# lab3_schematic.net
KiCad netlist of a schematic drawn in Altium Designer
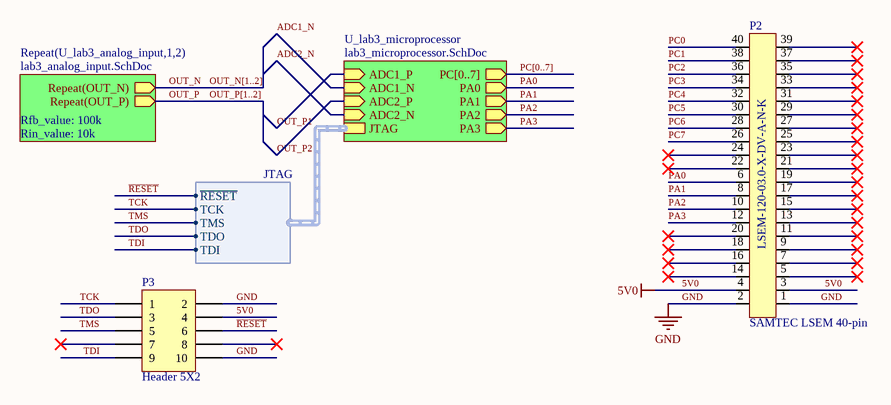
[diagram p0: lab3_schematic.SchDoc]

(export (version "E")
  (design (tool "Eeschema 10.0.6"))
  (components
    (comp (ref "P2")
      (value "SAMTEC LSEM 40-pin")
      (footprint "PcbLib_MW:LSEM-120-03.0-L-DV-A-N-K-TR")
      (fields (field (name "MANUFACTURER") "SAMTEC") (field (name "PART NUMBER") "LSEM-120-03.0-X-DV-A-N-K"))
      (libsource (lib "Schlib_MW") (part "LSEM-120-03.0-X-DV-A-N-K"))
    )
    (comp (ref "P3")
      (value "Header 5X2")
      (footprint "HDR2X5")
      (description "Header, 5-Pin, Dual row")
      (fields (field (name "PUBLISHER") "Altium Limited"))
      (libsource (lib "Miscellaneous Connectors") (part "Header 5X2"))
    )
  )
  (nets
    (net (code "12") (name "/PA0") (class "Default")
      (node (ref "P2") (pin "6") (pinfunction "4_6") (pintype "passive"))
    )
    (net (code "13") (name "/PA1") (class "Default")
      (node (ref "P2") (pin "8") (pinfunction "5_8") (pintype "passive"))
    )
    (net (code "14") (name "/PA2") (class "Default")
      (node (ref "P2") (pin "10") (pinfunction "6_10") (pintype "passive"))
    )
    (net (code "15") (name "/PA3") (class "Default")
      (node (ref "P2") (pin "12") (pinfunction "7_12") (pintype "passive"))
    )
    (net (code "16") (name "/PC0") (class "Default")
      (node (ref "P2") (pin "40") (pinfunction "21_40") (pintype "passive"))
    )
    (net (code "17") (name "/PC1") (class "Default")
      (node (ref "P2") (pin "38") (pinfunction "20_38") (pintype "passive"))
    )
    (net (code "18") (name "/PC2") (class "Default")
      (node (ref "P2") (pin "36") (pinfunction "19_36") (pintype "passive"))
    )
    (net (code "19") (name "/PC3") (class "Default")
      (node (ref "P2") (pin "34") (pinfunction "18_34") (pintype "passive"))
    )
    (net (code "20") (name "/PC4") (class "Default")
      (node (ref "P2") (pin "32") (pinfunction "17_32") (pintype "passive"))
    )
    (net (code "21") (name "/PC5") (class "Default")
      (node (ref "P2") (pin "30") (pinfunction "16_30") (pintype "passive"))
    )
    (net (code "22") (name "/PC6") (class "Default")
      (node (ref "P2") (pin "28") (pinfunction "15_28") (pintype "passive"))
    )
    (net (code "23") (name "/PC7") (class "Default")
      (node (ref "P2") (pin "26") (pinfunction "14_26") (pintype "passive"))
    )
    (net (code "25") (name "/TCK") (class "Default")
      (node (ref "P3") (pin "1") (pinfunction "1_1") (pintype "passive"))
    )
    (net (code "26") (name "/TDI") (class "Default")
      (node (ref "P3") (pin "9") (pinfunction "9_9") (pintype "passive"))
    )
    (net (code "27") (name "/TDO") (class "Default")
      (node (ref "P3") (pin "3") (pinfunction "3_3") (pintype "passive"))
    )
    (net (code "28") (name "/TMS") (class "Default")
      (node (ref "P3") (pin "5") (pinfunction "5_5") (pintype "passive"))
    )
    (net (code "30") (name "/~{RESET}") (class "Default")
      (node (ref "P3") (pin "6") (pinfunction "6_6") (pintype "passive"))
    )
    (net (code "31") (name "5V0") (class "Default")
      (node (ref "P2") (pin "3") (pinfunction "2_3") (pintype "passive"))
      (node (ref "P2") (pin "4") (pinfunction "3_4") (pintype "passive"))
      (node (ref "P3") (pin "4") (pinfunction "4_4") (pintype "passive"))
    )
    (net (code "32") (name "GND") (class "Default")
      (node (ref "P2") (pin "1") (pinfunction "1_1") (pintype "passive"))
      (node (ref "P2") (pin "2") (pinfunction "2_2") (pintype "passive"))
      (node (ref "P3") (pin "10") (pinfunction "10_10") (pintype "passive"))
      (node (ref "P3") (pin "2") (pinfunction "2_2") (pintype "passive"))
    )
    (net (code "33") (name "unconnected-(P2-3-Pad5)") (class "Default")
      (node (ref "P2") (pin "5") (pinfunction "3_5") (pintype "passive+no_connect"))
    )
    (net (code "34") (name "unconnected-(P2-4-Pad7)") (class "Default")
      (node (ref "P2") (pin "7") (pinfunction "4_7") (pintype "passive+no_connect"))
    )
    (net (code "35") (name "unconnected-(P2-5-Pad9)") (class "Default")
      (node (ref "P2") (pin "9") (pinfunction "5_9") (pintype "passive+no_connect"))
    )
    (net (code "36") (name "unconnected-(P2-6-Pad11)") (class "Default")
      (node (ref "P2") (pin "11") (pinfunction "6_11") (pintype "passive+no_connect"))
    )
    (net (code "37") (name "unconnected-(P2-7-Pad13)") (class "Default")
      (node (ref "P2") (pin "13") (pinfunction "7_13") (pintype "passive+no_connect"))
    )
    (net (code "38") (name "unconnected-(P2-8-Pad14)") (class "Default")
      (node (ref "P2") (pin "14") (pinfunction "8_14") (pintype "passive+no_connect"))
    )
    (net (code "39") (name "unconnected-(P2-8-Pad15)") (class "Default")
      (node (ref "P2") (pin "15") (pinfunction "8_15") (pintype "passive+no_connect"))
    )
    (net (code "40") (name "unconnected-(P2-9-Pad16)") (class "Default")
      (node (ref "P2") (pin "16") (pinfunction "9_16") (pintype "passive+no_connect"))
    )
    (net (code "41") (name "unconnected-(P2-9-Pad17)") (class "Default")
      (node (ref "P2") (pin "17") (pinfunction "9_17") (pintype "passive+no_connect"))
    )
    (net (code "42") (name "unconnected-(P2-10-Pad18)") (class "Default")
      (node (ref "P2") (pin "18") (pinfunction "10_18") (pintype "passive+no_connect"))
    )
    (net (code "43") (name "unconnected-(P2-10-Pad19)") (class "Default")
      (node (ref "P2") (pin "19") (pinfunction "10_19") (pintype "passive+no_connect"))
    )
    (net (code "44") (name "unconnected-(P2-11-Pad20)") (class "Default")
      (node (ref "P2") (pin "20") (pinfunction "11_20") (pintype "passive+no_connect"))
    )
    (net (code "45") (name "unconnected-(P2-11-Pad21)") (class "Default")
      (node (ref "P2") (pin "21") (pinfunction "11_21") (pintype "passive+no_connect"))
    )
    (net (code "46") (name "unconnected-(P2-12-Pad22)") (class "Default")
      (node (ref "P2") (pin "22") (pinfunction "12_22") (pintype "passive+no_connect"))
    )
    (net (code "47") (name "unconnected-(P2-12-Pad23)") (class "Default")
      (node (ref "P2") (pin "23") (pinfunction "12_23") (pintype "passive+no_connect"))
    )
    (net (code "48") (name "unconnected-(P2-13-Pad24)") (class "Default")
      (node (ref "P2") (pin "24") (pinfunction "13_24") (pintype "passive+no_connect"))
    )
    (net (code "49") (name "unconnected-(P2-13-Pad25)") (class "Default")
      (node (ref "P2") (pin "25") (pinfunction "13_25") (pintype "passive+no_connect"))
    )
    (net (code "50") (name "unconnected-(P2-14-Pad27)") (class "Default")
      (node (ref "P2") (pin "27") (pinfunction "14_27") (pintype "passive+no_connect"))
    )
    (net (code "51") (name "unconnected-(P2-15-Pad29)") (class "Default")
      (node (ref "P2") (pin "29") (pinfunction "15_29") (pintype "passive+no_connect"))
    )
    (net (code "52") (name "unconnected-(P2-16-Pad31)") (class "Default")
      (node (ref "P2") (pin "31") (pinfunction "16_31") (pintype "passive+no_connect"))
    )
    (net (code "53") (name "unconnected-(P2-17-Pad33)") (class "Default")
      (node (ref "P2") (pin "33") (pinfunction "17_33") (pintype "passive+no_connect"))
    )
    (net (code "54") (name "unconnected-(P2-18-Pad35)") (class "Default")
      (node (ref "P2") (pin "35") (pinfunction "18_35") (pintype "passive+no_connect"))
    )
    (net (code "55") (name "unconnected-(P2-19-Pad37)") (class "Default")
      (node (ref "P2") (pin "37") (pinfunction "19_37") (pintype "passive+no_connect"))
    )
    (net (code "56") (name "unconnected-(P2-20-Pad39)") (class "Default")
      (node (ref "P2") (pin "39") (pinfunction "20_39") (pintype "passive+no_connect"))
    )
    (net (code "57") (name "unconnected-(P3-Pad7)") (class "Default")
      (node (ref "P3") (pin "7") (pinfunction "7_7") (pintype "passive+no_connect"))
    )
    (net (code "58") (name "unconnected-(P3-Pad8)") (class "Default")
      (node (ref "P3") (pin "8") (pinfunction "8_8") (pintype "passive+no_connect"))
    )
  )
)
